# RS485_M_V1.net
KiCad netlist of a schematic drawn in Altium Designer
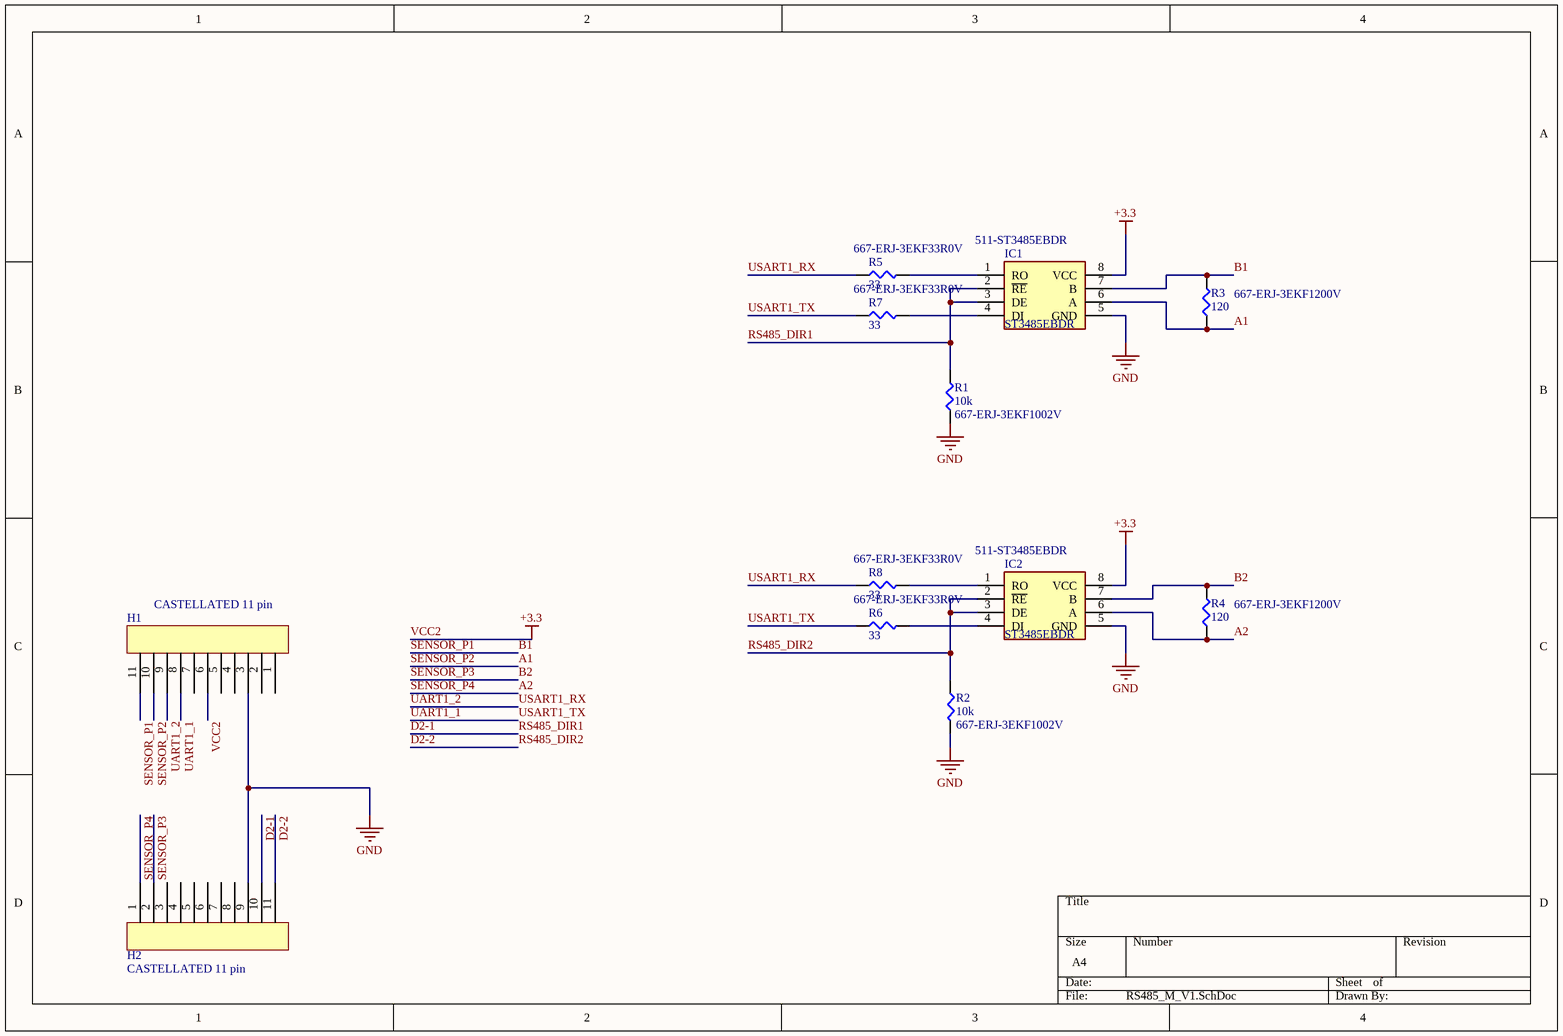
[diagram p0: RS485_M_V1.SchDoc]

(export (version "E")
  (design (tool "Eeschema 10.0.6"))
  (components
    (comp (ref "H1")
      (value "CASTELLATED 11 pin")
      (footprint "CASTELLATED 11 pin")
      (libsource (lib "") (part "CASTELLATED 11 pin_1"))
    )
    (comp (ref "H2")
      (value "CASTELLATED 11 pin")
      (footprint "CASTELLATED 11 pin")
      (libsource (lib "USIB") (part "CASTELLATED 11 pin"))
    )
    (comp (ref "IC1")
      (value "ST3485EBDR")
      (footprint "SamacSys:SOIC127P600X175-8N")
      (description "Integrated Circuit")
      (fields
        (field (name "MOUSER2 PART NUMBER") "511-ST3485EBDR")
        (field (name "SUPPLIER PART NUMBER 1") "511-ST3485EBDR")
      )
      (libsource (lib "*") (part "ST3485EBDR"))
    )
    (comp (ref "IC2")
      (value "ST3485EBDR")
      (footprint "SamacSys:SOIC127P600X175-8N")
      (description "Integrated Circuit")
      (fields
        (field (name "MOUSER2 PART NUMBER") "511-ST3485EBDR")
        (field (name "SUPPLIER PART NUMBER 1") "511-ST3485EBDR")
      )
      (libsource (lib "*") (part "ST3485EBDR"))
    )
    (comp (ref "R1")
      (value "10k")
      (footprint "SMD-0603-RES")
      (description "RES SMD 10K OHM 1% 1/10W 0603")
      (fields
        (field (name "PART NUMBER") "ERJ-3EKF1002V")
        (field (name "DIGI-KEY PART NUMBER") "P10.0KHCT-ND")
        (field (name "SUPPLIER PART NUMBER 1") "667-ERJ-3EKF1002V")
      )
      (libsource (lib "Panasonic_ERJ_0603") (part "ERJ-3EKF1002V"))
    )
    (comp (ref "R2")
      (value "10k")
      (footprint "SMD-0603-RES")
      (description "RES SMD 10K OHM 1% 1/10W 0603")
      (fields
        (field (name "PART NUMBER") "ERJ-3EKF1002V")
        (field (name "DIGI-KEY PART NUMBER") "P10.0KHCT-ND")
        (field (name "SUPPLIER PART NUMBER 1") "667-ERJ-3EKF1002V")
      )
      (libsource (lib "Panasonic_ERJ_0603") (part "ERJ-3EKF1002V"))
    )
    (comp (ref "R3")
      (value "120")
      (footprint "SMD-0603-RES")
      (description "RES SMD 120 OHM 1% 1/10W 0603")
      (fields
        (field (name "PART NUMBER") "ERJ-3EKF1200V")
        (field (name "DIGI-KEY PART NUMBER") "P120HCT-ND")
        (field (name "SUPPLIER PART NUMBER 1") "667-ERJ-3EKF1200V")
      )
      (libsource (lib "Panasonic_ERJ_0603") (part "ERJ-3EKF1200V"))
    )
    (comp (ref "R4")
      (value "120")
      (footprint "SMD-0603-RES")
      (description "RES SMD 120 OHM 1% 1/10W 0603")
      (fields
        (field (name "PART NUMBER") "ERJ-3EKF1200V")
        (field (name "DIGI-KEY PART NUMBER") "P120HCT-ND")
        (field (name "SUPPLIER PART NUMBER 1") "667-ERJ-3EKF1200V")
      )
      (libsource (lib "Panasonic_ERJ_0603") (part "ERJ-3EKF1200V"))
    )
    (comp (ref "R5")
      (value "33")
      (footprint "SMD-0603-RES")
      (description "RES SMD 33 OHM 1% 1/10W 0603")
      (fields
        (field (name "PART NUMBER") "ERJ-3EKF33R0V")
        (field (name "DIGI-KEY PART NUMBER") "P33.0HCT-ND")
        (field (name "SUPPLIER PART NUMBER 1") "667-ERJ-3EKF33R0V")
      )
      (libsource (lib "Panasonic_ERJ_0603") (part "ERJ-3EKF33R0V"))
    )
    (comp (ref "R6")
      (value "33")
      (footprint "SMD-0603-RES")
      (description "RES SMD 33 OHM 1% 1/10W 0603")
      (fields
        (field (name "PART NUMBER") "ERJ-3EKF33R0V")
        (field (name "DIGI-KEY PART NUMBER") "P33.0HCT-ND")
        (field (name "SUPPLIER PART NUMBER 1") "667-ERJ-3EKF33R0V")
      )
      (libsource (lib "Panasonic_ERJ_0603") (part "ERJ-3EKF33R0V"))
    )
    (comp (ref "R7")
      (value "33")
      (footprint "SMD-0603-RES")
      (description "RES SMD 33 OHM 1% 1/10W 0603")
      (fields
        (field (name "PART NUMBER") "ERJ-3EKF33R0V")
        (field (name "DIGI-KEY PART NUMBER") "P33.0HCT-ND")
        (field (name "SUPPLIER PART NUMBER 1") "667-ERJ-3EKF33R0V")
      )
      (libsource (lib "Panasonic_ERJ_0603") (part "ERJ-3EKF33R0V"))
    )
    (comp (ref "R8")
      (value "33")
      (footprint "SMD-0603-RES")
      (description "RES SMD 33 OHM 1% 1/10W 0603")
      (fields
        (field (name "PART NUMBER") "ERJ-3EKF33R0V")
        (field (name "DIGI-KEY PART NUMBER") "P33.0HCT-ND")
        (field (name "SUPPLIER PART NUMBER 1") "667-ERJ-3EKF33R0V")
      )
      (libsource (lib "Panasonic_ERJ_0603") (part "ERJ-3EKF33R0V"))
    )
  )
  (nets
    (net (code "1") (name "+3.3") (class "Default")
      (node (ref "H1") (pin "6") (pintype "passive"))
      (node (ref "IC1") (pin "8") (pinfunction "VCC_8") (pintype "passive"))
      (node (ref "IC2") (pin "8") (pinfunction "VCC_8") (pintype "passive"))
    )
    (net (code "2") (name "/A1") (class "Default")
      (node (ref "H1") (pin "10") (pintype "passive"))
      (node (ref "IC1") (pin "6") (pinfunction "A_6") (pintype "passive"))
      (node (ref "R3") (pin "1") (pinfunction "1_1") (pintype "passive"))
    )
    (net (code "3") (name "/A2") (class "Default")
      (node (ref "H2") (pin "1") (pintype "passive"))
      (node (ref "IC2") (pin "6") (pinfunction "A_6") (pintype "passive"))
      (node (ref "R4") (pin "1") (pinfunction "1_1") (pintype "passive"))
    )
    (net (code "4") (name "/B1") (class "Default")
      (node (ref "H1") (pin "11") (pintype "passive"))
      (node (ref "IC1") (pin "7") (pinfunction "B_7") (pintype "passive"))
      (node (ref "R3") (pin "2") (pinfunction "2_2") (pintype "passive"))
    )
    (net (code "5") (name "/B2") (class "Default")
      (node (ref "H2") (pin "2") (pintype "passive"))
      (node (ref "IC2") (pin "7") (pinfunction "B_7") (pintype "passive"))
      (node (ref "R4") (pin "2") (pinfunction "2_2") (pintype "passive"))
    )
    (net (code "6") (name "/D2-1") (class "Default")
      (node (ref "H2") (pin "10") (pintype "passive"))
      (node (ref "IC1") (pin "2") (pinfunction "~{RE}_2") (pintype "passive"))
      (node (ref "IC1") (pin "3") (pinfunction "DE_3") (pintype "passive"))
      (node (ref "R1") (pin "2") (pinfunction "2_2") (pintype "passive"))
    )
    (net (code "7") (name "/D2-2") (class "Default")
      (node (ref "H2") (pin "11") (pintype "passive"))
      (node (ref "IC2") (pin "2") (pinfunction "~{RE}_2") (pintype "passive"))
      (node (ref "IC2") (pin "3") (pinfunction "DE_3") (pintype "passive"))
      (node (ref "R2") (pin "1") (pinfunction "1_1") (pintype "passive"))
    )
    (net (code "8") (name "/UART1_1") (class "Default")
      (node (ref "H1") (pin "8") (pintype "passive"))
      (node (ref "R6") (pin "1") (pinfunction "1_1") (pintype "passive"))
      (node (ref "R7") (pin "1") (pinfunction "1_1") (pintype "passive"))
    )
    (net (code "9") (name "/UART1_2") (class "Default")
      (node (ref "H1") (pin "9") (pintype "passive"))
      (node (ref "R5") (pin "1") (pinfunction "1_1") (pintype "passive"))
      (node (ref "R8") (pin "1") (pinfunction "1_1") (pintype "passive"))
    )
    (net (code "10") (name "GND") (class "Default")
      (node (ref "H1") (pin "3") (pintype "passive"))
      (node (ref "H2") (pin "9") (pintype "passive"))
      (node (ref "IC1") (pin "5") (pinfunction "GND_5") (pintype "passive"))
      (node (ref "IC2") (pin "5") (pinfunction "GND_5") (pintype "passive"))
      (node (ref "R1") (pin "1") (pinfunction "1_1") (pintype "passive"))
      (node (ref "R2") (pin "2") (pinfunction "2_2") (pintype "passive"))
    )
    (net (code "11") (name "Net-(IC1-DI)") (class "Default")
      (node (ref "IC1") (pin "4") (pinfunction "DI_4") (pintype "passive"))
      (node (ref "R7") (pin "2") (pinfunction "2_2") (pintype "passive"))
    )
    (net (code "12") (name "Net-(IC1-RO)") (class "Default")
      (node (ref "IC1") (pin "1") (pinfunction "RO_1") (pintype "passive"))
      (node (ref "R5") (pin "2") (pinfunction "2_2") (pintype "passive"))
    )
    (net (code "13") (name "Net-(IC2-DI)") (class "Default")
      (node (ref "IC2") (pin "4") (pinfunction "DI_4") (pintype "passive"))
      (node (ref "R6") (pin "2") (pinfunction "2_2") (pintype "passive"))
    )
    (net (code "14") (name "Net-(IC2-RO)") (class "Default")
      (node (ref "IC2") (pin "1") (pinfunction "RO_1") (pintype "passive"))
      (node (ref "R8") (pin "2") (pinfunction "2_2") (pintype "passive"))
    )
    (net (code "15") (name "unconnected-(H1-Pad1)") (class "Default")
      (node (ref "H1") (pin "1") (pintype "passive"))
    )
    (net (code "16") (name "unconnected-(H1-Pad2)") (class "Default")
      (node (ref "H1") (pin "2") (pintype "passive"))
    )
    (net (code "17") (name "unconnected-(H1-Pad4)") (class "Default")
      (node (ref "H1") (pin "4") (pintype "passive"))
    )
    (net (code "18") (name "unconnected-(H1-Pad5)") (class "Default")
      (node (ref "H1") (pin "5") (pintype "passive"))
    )
    (net (code "19") (name "unconnected-(H1-Pad7)") (class "Default")
      (node (ref "H1") (pin "7") (pintype "passive"))
    )
    (net (code "20") (name "unconnected-(H2-Pad3)") (class "Default")
      (node (ref "H2") (pin "3") (pintype "passive"))
    )
    (net (code "21") (name "unconnected-(H2-Pad4)") (class "Default")
      (node (ref "H2") (pin "4") (pintype "passive"))
    )
    (net (code "22") (name "unconnected-(H2-Pad5)") (class "Default")
      (node (ref "H2") (pin "5") (pintype "passive"))
    )
    (net (code "23") (name "unconnected-(H2-Pad6)") (class "Default")
      (node (ref "H2") (pin "6") (pintype "passive"))
    )
    (net (code "24") (name "unconnected-(H2-Pad7)") (class "Default")
      (node (ref "H2") (pin "7") (pintype "passive"))
    )
    (net (code "25") (name "unconnected-(H2-Pad8)") (class "Default")
      (node (ref "H2") (pin "8") (pintype "passive"))
    )
  )
)
